# Adafruit_SWD_Breakout.net
KiCad netlist of a schematic drawn in EAGLE
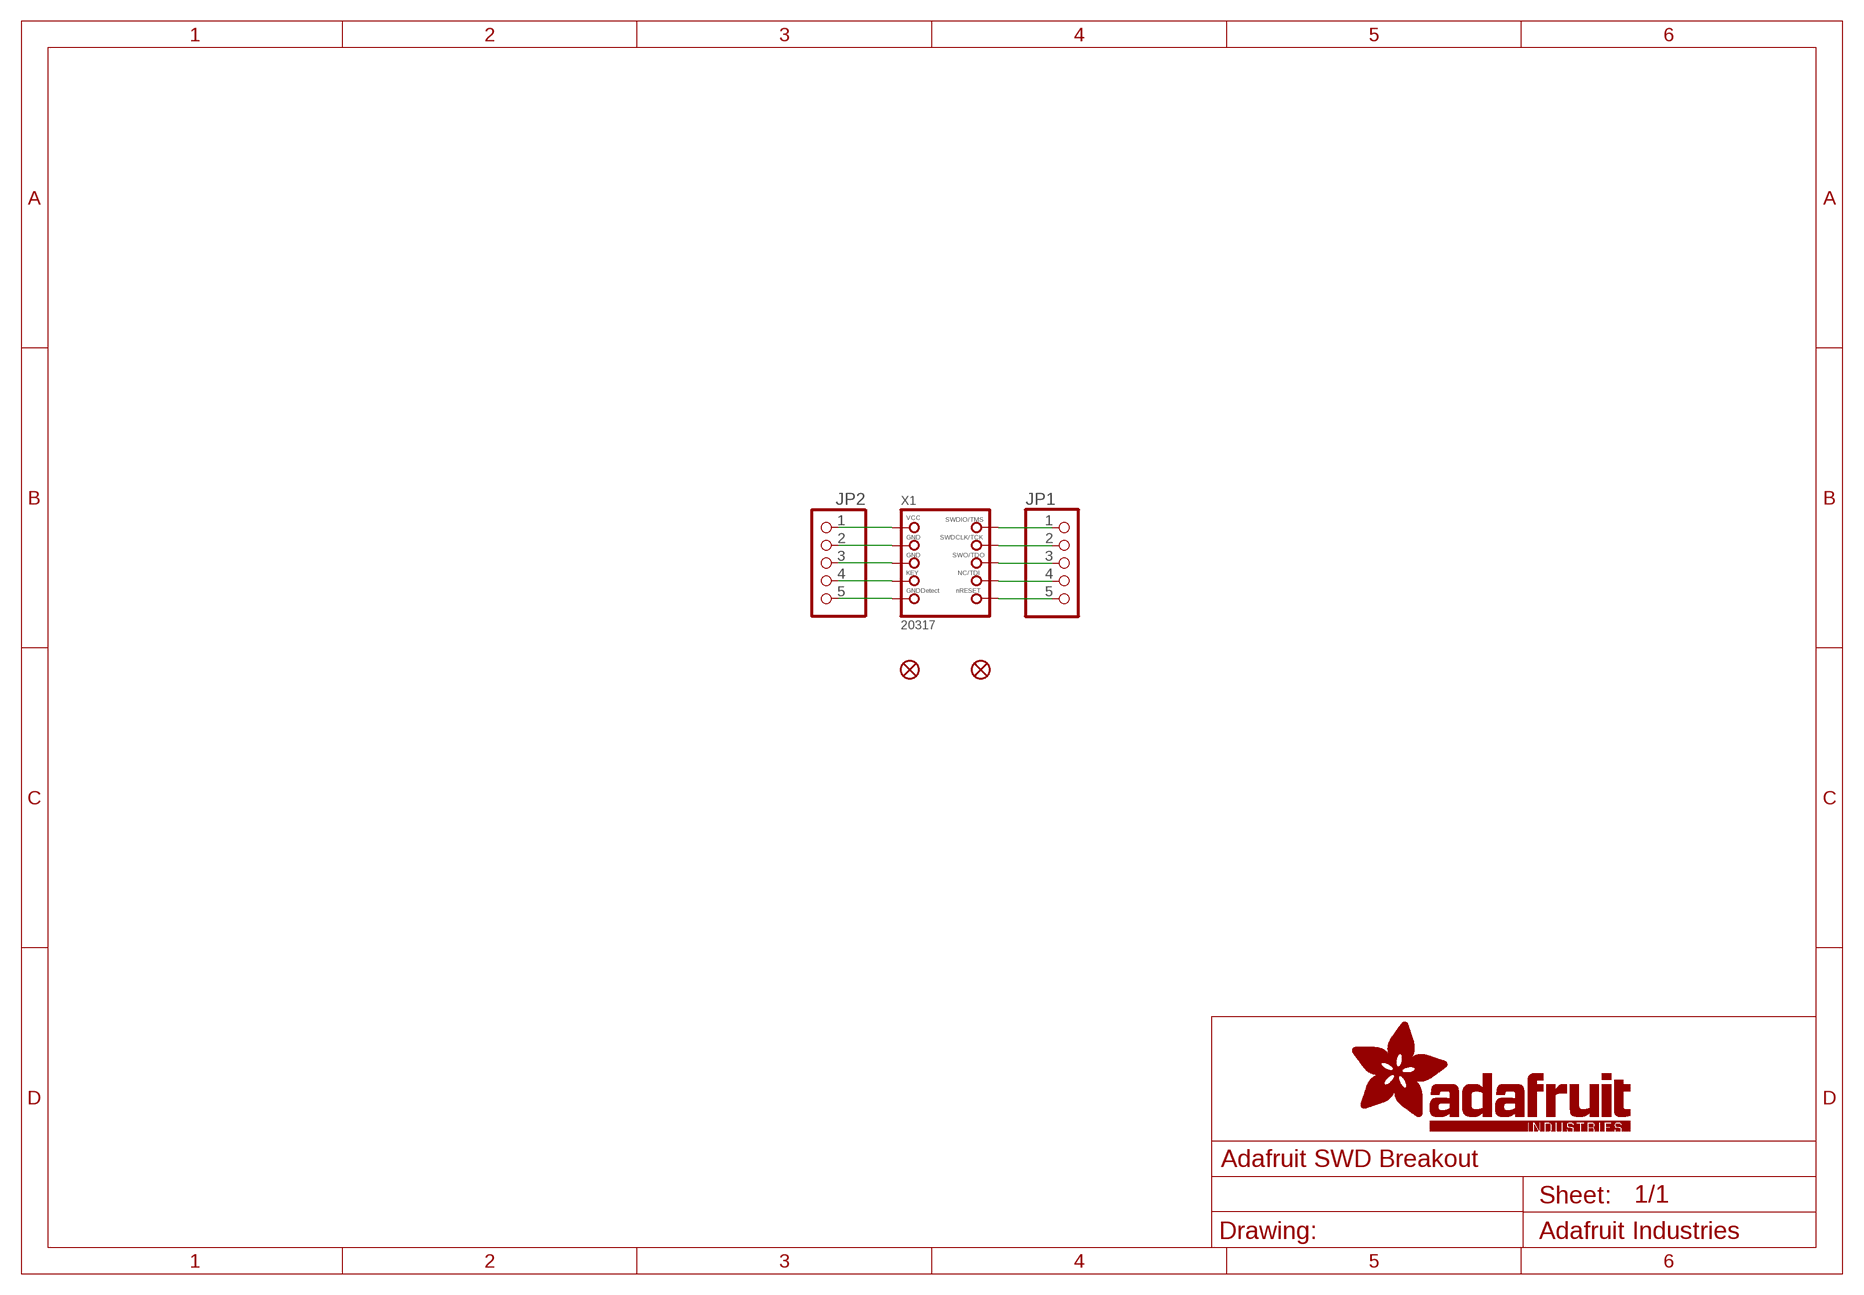
[diagram p0: schematic, sheet 1]

(export (version "E")
  (design (tool "Eeschema 10.0.6"))
  (components
    (comp (ref "FID1")
      (value "FIDUCIAL\"\"")
      (footprint "eagle-import:FIDUCIAL_1MM")
      (libsource (lib "eagle-import") (part "FIDUCIAL{dblquote}{dblquote}"))
    )
    (comp (ref "FID2")
      (value "FIDUCIAL\"\"")
      (footprint "eagle-import:FIDUCIAL_1MM")
      (libsource (lib "eagle-import") (part "FIDUCIAL{dblquote}{dblquote}"))
    )
    (comp (ref "JP1")
      (value "HEADER-1X576MIL_FULL")
      (footprint "eagle-import:1X05_ROUND_FULL_76")
      (libsource (lib "eagle-import") (part "HEADER-1X576MIL_FULL"))
    )
    (comp (ref "JP2")
      (value "HEADER-1X576MIL_FULL")
      (footprint "eagle-import:1X05_ROUND_FULL_76")
      (libsource (lib "eagle-import") (part "HEADER-1X576MIL_FULL"))
    )
    (comp (ref "X1")
      (value "20317")
      (footprint "eagle-import:2X05_1.27MM_BOX_POSTS")
      (libsource (lib "eagle-import") (part "JTAG-CORTEXBOXPOSTS"))
    )
  )
  (nets
    (net (code "1") (name "Net-(JP2-Pad2)") (class "Default")
      (node (ref "JP2") (pin "2") (pinfunction "2_2") (pintype "passive"))
      (node (ref "X1") (pin "3") (pinfunction "GND_3") (pintype "power_in"))
    )
    (net (code "2") (name "Net-(JP2-Pad3)") (class "Default")
      (node (ref "JP2") (pin "3") (pinfunction "3_3") (pintype "passive"))
      (node (ref "X1") (pin "5") (pinfunction "GND_5") (pintype "power_in"))
    )
    (net (code "3") (name "Net-(X1-GNDDETECT)") (class "Default")
      (node (ref "JP2") (pin "5") (pinfunction "5_5") (pintype "passive"))
      (node (ref "X1") (pin "9") (pinfunction "GNDDETECT_9") (pintype "bidirectional"))
    )
    (net (code "4") (name "Net-(X1-KEY)") (class "Default")
      (node (ref "JP2") (pin "4") (pinfunction "4_4") (pintype "passive"))
      (node (ref "X1") (pin "7") (pinfunction "KEY_7") (pintype "bidirectional"))
    )
    (net (code "5") (name "Net-(X1-NRESET)") (class "Default")
      (node (ref "JP1") (pin "5") (pinfunction "5_5") (pintype "passive"))
      (node (ref "X1") (pin "10") (pinfunction "NRESET_10") (pintype "bidirectional"))
    )
    (net (code "6") (name "Net-(X1-SWDCLK)") (class "Default")
      (node (ref "JP1") (pin "2") (pinfunction "2_2") (pintype "passive"))
      (node (ref "X1") (pin "4") (pinfunction "SWDCLK_4") (pintype "bidirectional"))
    )
    (net (code "7") (name "Net-(X1-SWDIO)") (class "Default")
      (node (ref "JP1") (pin "1") (pinfunction "1_1") (pintype "passive"))
      (node (ref "X1") (pin "2") (pinfunction "SWDIO_2") (pintype "bidirectional"))
    )
    (net (code "8") (name "Net-(X1-SWO)") (class "Default")
      (node (ref "JP1") (pin "3") (pinfunction "3_3") (pintype "passive"))
      (node (ref "X1") (pin "6") (pinfunction "SWO_6") (pintype "bidirectional"))
    )
    (net (code "9") (name "Net-(X1-TDI)") (class "Default")
      (node (ref "JP1") (pin "4") (pinfunction "4_4") (pintype "passive"))
      (node (ref "X1") (pin "8") (pinfunction "TDI_8") (pintype "bidirectional"))
    )
    (net (code "10") (name "Net-(X1-VCC)") (class "Default")
      (node (ref "JP2") (pin "1") (pinfunction "1_1") (pintype "passive"))
      (node (ref "X1") (pin "1") (pinfunction "VCC_1") (pintype "power_in"))
    )
  )
)
